# tetris.net
KiCad netlist of a schematic drawn in Altium Designer
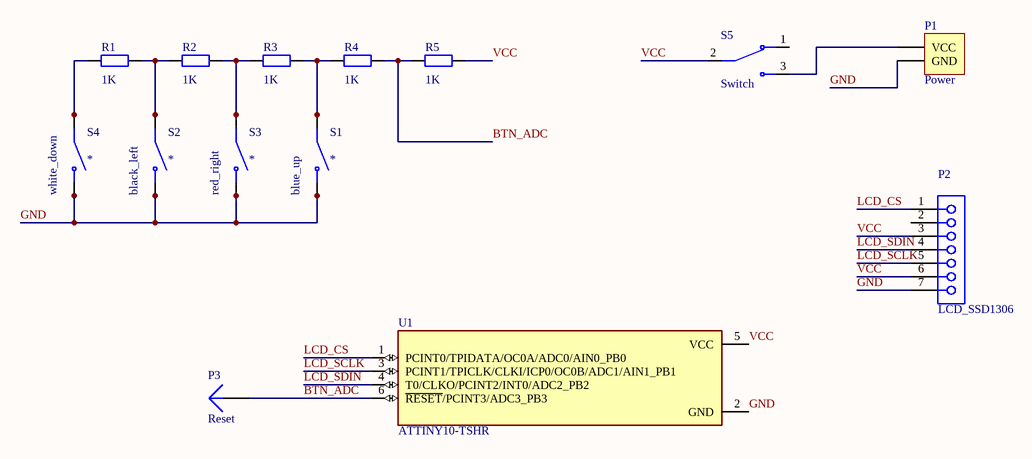
[diagram p0: tetris.SchDoc]

(export (version "E")
  (design (tool "Eeschema 10.0.6"))
  (components
    (comp (ref "P1")
      (value "Power")
      (footprint "HDR1X2")
      (description "Header, 2-Pin")
      (fields (field (name "PUBLISHER") "Altium Limited"))
      (libsource (lib "Miscellaneous Connectors") (part "Header 2"))
    )
    (comp (ref "P2")
      (value "LCD_SSD1306")
      (footprint "61300711821")
      (description "WR-PHD Socket Header, THT, Vertical, pitch 2.54mm, 1 Row, 7P")
      (fields
        (field (name "MANUFACTURER PART NUMBER") "61300711821")
        (field (name "MANUFACTURER") "Wurth Elektronik")
      )
      (libsource (lib "pls_header_x7_2.54") (part "61300711821"))
    )
    (comp (ref "P3")
      (value "Reset")
      (footprint "PIN1")
      (description "Plug")
      (fields (field (name "PUBLISHER") "Altium Limited"))
      (libsource (lib "Miscellaneous Connectors") (part "Plug"))
    )
    (comp (ref "R1")
      (value "1K")
      (footprint "AXIAL-0.4")
      (description "Resistor")
      (fields (field (name "PUBLISHER") "Altium Limited"))
      (libsource (lib "Miscellaneous Devices") (part "Res2"))
    )
    (comp (ref "R2")
      (value "1K")
      (footprint "AXIAL-0.4")
      (description "Resistor")
      (fields (field (name "PUBLISHER") "Altium Limited"))
      (libsource (lib "Miscellaneous Devices") (part "Res2"))
    )
    (comp (ref "R3")
      (value "1K")
      (footprint "AXIAL-0.4")
      (description "Resistor")
      (fields (field (name "PUBLISHER") "Altium Limited"))
      (libsource (lib "Miscellaneous Devices") (part "Res2"))
    )
    (comp (ref "R4")
      (value "1K")
      (footprint "AXIAL-0.4")
      (description "Resistor")
      (fields (field (name "PUBLISHER") "Altium Limited"))
      (libsource (lib "Miscellaneous Devices") (part "Res2"))
    )
    (comp (ref "R5")
      (value "1K")
      (footprint "AXIAL-0.4")
      (description "Resistor")
      (fields (field (name "PUBLISHER") "Altium Limited"))
      (libsource (lib "Miscellaneous Devices") (part "Res2"))
    )
    (comp (ref "S1")
      (value "blue_up")
      (footprint "SW_1571627-1")
      (fields
        (field (name "MF") "TE Connectivity")
        (field (name "MP") "FSM103A")
        (field (name "COMMENT_1") "*")
      )
      (libsource (lib "FSM103A") (part "FSM103A"))
    )
    (comp (ref "S2")
      (value "black_left")
      (footprint "SW_1571627-1")
      (fields
        (field (name "MF") "TE Connectivity")
        (field (name "MP") "FSM103A")
        (field (name "COMMENT_1") "*")
      )
      (libsource (lib "FSM103A") (part "FSM103A"))
    )
    (comp (ref "S3")
      (value "red_right")
      (footprint "SW_1571627-1")
      (fields
        (field (name "MF") "TE Connectivity")
        (field (name "MP") "FSM103A")
        (field (name "COMMENT_1") "*")
      )
      (libsource (lib "FSM103A") (part "FSM103A"))
    )
    (comp (ref "S4")
      (value "white_down")
      (footprint "SW_1571627-1")
      (fields
        (field (name "MF") "TE Connectivity")
        (field (name "MP") "FSM103A")
        (field (name "COMMENT_1") "*")
      )
      (libsource (lib "FSM103A") (part "FSM103A"))
    )
    (comp (ref "S5")
      (value "Switch")
      (footprint "SW_EG1270")
      (description "Slide Switch SPDT Through Hole, Right Angle")
      (fields (field (name "MF") "E-Switch") (field (name "MP") "EG1270"))
      (libsource (lib "switch_3pin") (part "EG1270"))
    )
    (comp (ref "U1")
      (value "ATTINY10-TSHR")
      (footprint "SOT95P280X145-6N")
      (description "AVR AVR® ATtiny Microcontroller IC 8-Bit 12MHz 1KB (512 x 16) FLASH SOT-23-6")
      (fields (field (name "MF") "Microchip"))
      (libsource (lib "ATTINY10-TSHR") (part "ATTINY10-TSHR"))
    )
  )
  (nets
    (net (code "1") (name "/BTN_ADC") (class "Default")
      (node (ref "P3") (pin "1") (pinfunction "1_1") (pintype "passive"))
      (node (ref "R4") (pin "2") (pinfunction "2_2") (pintype "passive"))
      (node (ref "R5") (pin "1") (pinfunction "1_1") (pintype "passive"))
      (node (ref "U1") (pin "6") (pinfunction "~{RESET}/PCINT3/ADC3_PB3_6") (pintype "bidirectional"))
    )
    (net (code "2") (name "/GND") (class "Default")
      (node (ref "P1") (pin "2") (pinfunction "GND_2") (pintype "passive"))
      (node (ref "P2") (pin "7") (pinfunction "7_7") (pintype "passive"))
      (node (ref "S1") (pin "3") (pinfunction "NO_3") (pintype "passive"))
      (node (ref "S1") (pin "4") (pinfunction "NO_4") (pintype "passive"))
      (node (ref "S2") (pin "3") (pinfunction "NO_3") (pintype "passive"))
      (node (ref "S2") (pin "4") (pinfunction "NO_4") (pintype "passive"))
      (node (ref "S3") (pin "3") (pinfunction "NO_3") (pintype "passive"))
      (node (ref "S3") (pin "4") (pinfunction "NO_4") (pintype "passive"))
      (node (ref "S4") (pin "3") (pinfunction "NO_3") (pintype "passive"))
      (node (ref "S4") (pin "4") (pinfunction "NO_4") (pintype "passive"))
      (node (ref "U1") (pin "2") (pinfunction "GND_2") (pintype "power_in"))
    )
    (net (code "3") (name "/LCD_CS") (class "Default")
      (node (ref "P2") (pin "1") (pinfunction "1_1") (pintype "passive"))
      (node (ref "U1") (pin "1") (pinfunction "PCINT0/TPIDATA/OC0A/ADC0/AIN0_PB0_1") (pintype "bidirectional"))
    )
    (net (code "4") (name "/LCD_SCLK") (class "Default")
      (node (ref "P2") (pin "5") (pinfunction "5_5") (pintype "passive"))
      (node (ref "U1") (pin "3") (pinfunction "PCINT1/TPICLK/CLKI/ICP0/OC0B/ADC1/AIN1_PB1_3") (pintype "bidirectional"))
    )
    (net (code "5") (name "/LCD_SDIN") (class "Default")
      (node (ref "P2") (pin "4") (pinfunction "4_4") (pintype "passive"))
      (node (ref "U1") (pin "4") (pinfunction "T0/CLKO/PCINT2/INT0/ADC2_PB2_4") (pintype "bidirectional"))
    )
    (net (code "6") (name "/VCC") (class "Default")
      (node (ref "P2") (pin "3") (pinfunction "3_3") (pintype "passive"))
      (node (ref "P2") (pin "6") (pinfunction "6_6") (pintype "passive"))
      (node (ref "R5") (pin "2") (pinfunction "2_2") (pintype "passive"))
      (node (ref "S5") (pin "2") (pinfunction "2_2") (pintype "passive"))
      (node (ref "U1") (pin "5") (pinfunction "VCC_5") (pintype "power_in"))
    )
    (net (code "7") (name "Net-(P1-VCC)") (class "Default")
      (node (ref "P1") (pin "1") (pinfunction "VCC_1") (pintype "passive"))
      (node (ref "S5") (pin "3") (pinfunction "3_3") (pintype "passive"))
    )
    (net (code "8") (name "Net-(R1-Pad1)") (class "Default")
      (node (ref "R1") (pin "1") (pinfunction "1_1") (pintype "passive"))
      (node (ref "S4") (pin "1") (pinfunction "COM_1") (pintype "passive"))
      (node (ref "S4") (pin "2") (pinfunction "COM_2") (pintype "passive"))
    )
    (net (code "9") (name "Net-(R1-Pad2)") (class "Default")
      (node (ref "R1") (pin "2") (pinfunction "2_2") (pintype "passive"))
      (node (ref "R2") (pin "1") (pinfunction "1_1") (pintype "passive"))
      (node (ref "S2") (pin "1") (pinfunction "COM_1") (pintype "passive"))
      (node (ref "S2") (pin "2") (pinfunction "COM_2") (pintype "passive"))
    )
    (net (code "10") (name "Net-(R2-Pad2)") (class "Default")
      (node (ref "R2") (pin "2") (pinfunction "2_2") (pintype "passive"))
      (node (ref "R3") (pin "1") (pinfunction "1_1") (pintype "passive"))
      (node (ref "S3") (pin "1") (pinfunction "COM_1") (pintype "passive"))
      (node (ref "S3") (pin "2") (pinfunction "COM_2") (pintype "passive"))
    )
    (net (code "11") (name "Net-(R3-Pad2)") (class "Default")
      (node (ref "R3") (pin "2") (pinfunction "2_2") (pintype "passive"))
      (node (ref "R4") (pin "1") (pinfunction "1_1") (pintype "passive"))
      (node (ref "S1") (pin "1") (pinfunction "COM_1") (pintype "passive"))
      (node (ref "S1") (pin "2") (pinfunction "COM_2") (pintype "passive"))
    )
    (net (code "12") (name "unconnected-(P2-Pad2)") (class "Default")
      (node (ref "P2") (pin "2") (pinfunction "2_2") (pintype "passive"))
    )
    (net (code "13") (name "unconnected-(S5-Pad1)") (class "Default")
      (node (ref "S5") (pin "1") (pinfunction "1_1") (pintype "passive"))
    )
  )
)
